# OECU_BASE5.net
KiCad netlist of a schematic drawn in Altium Designer
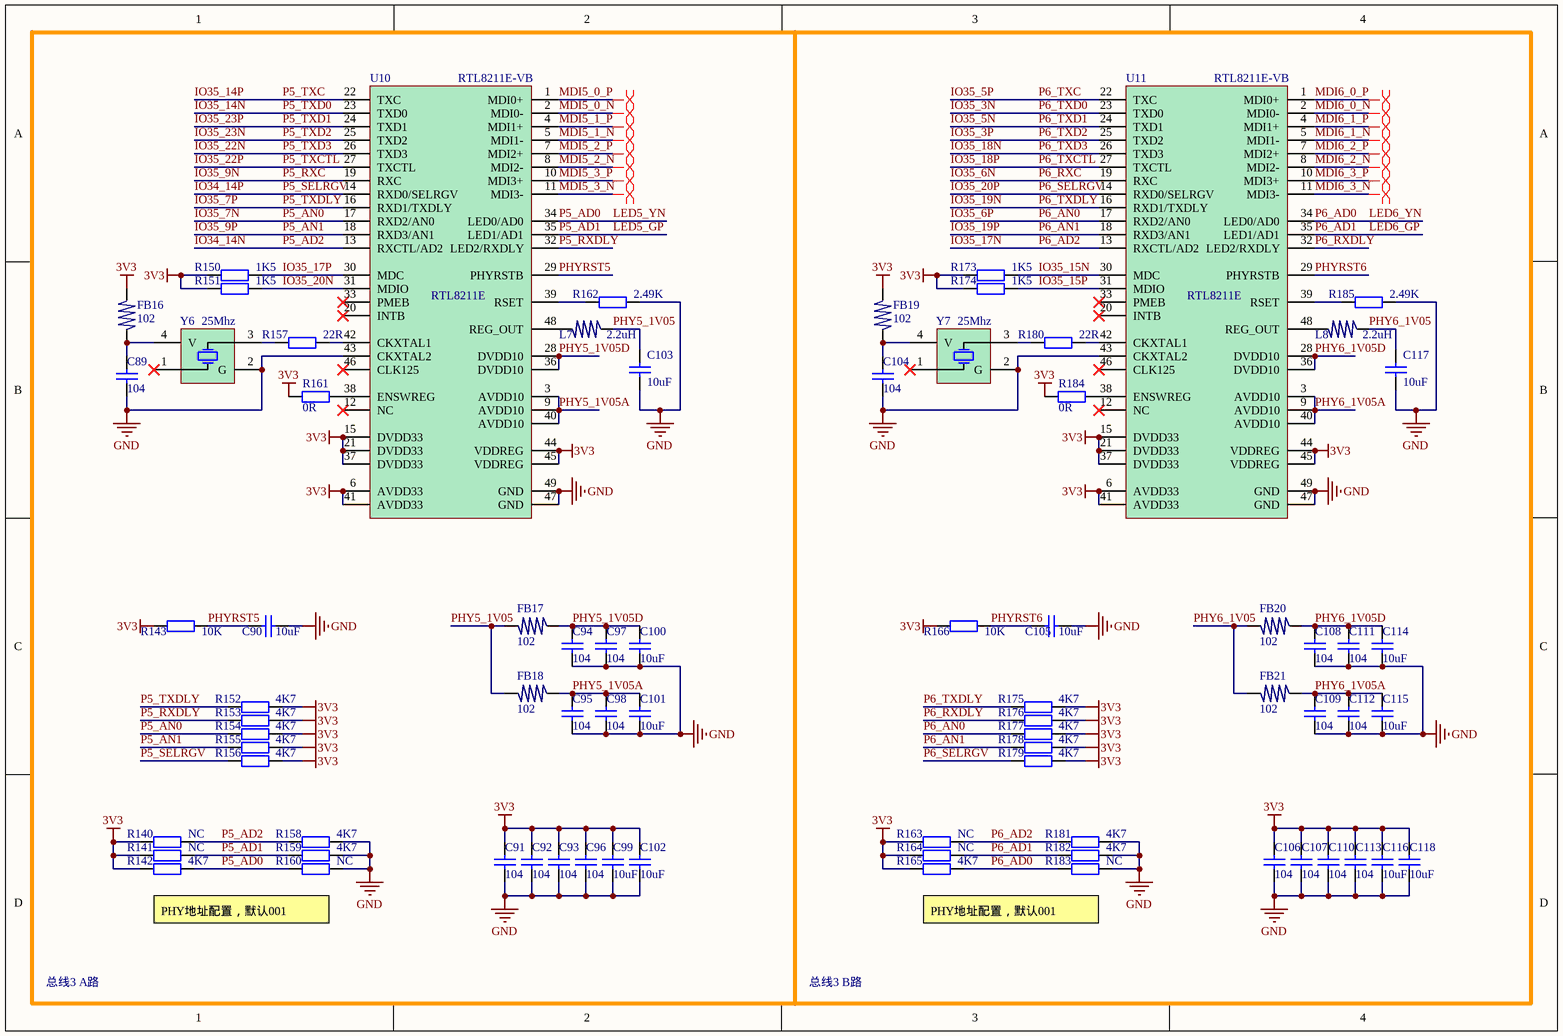
[diagram p0: OECU_BASE5.SchDoc]

(export (version "E")
  (design (tool "Eeschema 10.0.6"))
  (components
    (comp (ref "C89")
      (value "104")
      (footprint "0402")
      (description "贴片电容 0402")
      (libsource (lib "MT_Device") (part "CAP_0402"))
    )
    (comp (ref "C90")
      (value "10uF")
      (footprint "0402")
      (description "贴片电容 0402")
      (libsource (lib "MT_Device") (part "CAP_0402"))
    )
    (comp (ref "C91")
      (value "104")
      (footprint "0402")
      (description "贴片电容 0402")
      (libsource (lib "MT_Device") (part "CAP_0402"))
    )
    (comp (ref "C92")
      (value "104")
      (footprint "0402")
      (description "贴片电容 0402")
      (libsource (lib "MT_Device") (part "CAP_0402"))
    )
    (comp (ref "C93")
      (value "104")
      (footprint "0402")
      (description "贴片电容 0402")
      (libsource (lib "MT_Device") (part "CAP_0402"))
    )
    (comp (ref "C94")
      (value "104")
      (footprint "0402")
      (description "贴片电容 0402")
      (libsource (lib "MT_Device") (part "CAP_0402"))
    )
    (comp (ref "C95")
      (value "104")
      (footprint "0402")
      (description "贴片电容 0402")
      (libsource (lib "MT_Device") (part "CAP_0402"))
    )
    (comp (ref "C96")
      (value "104")
      (footprint "0402")
      (description "贴片电容 0402")
      (libsource (lib "MT_Device") (part "CAP_0402"))
    )
    (comp (ref "C97")
      (value "104")
      (footprint "0402")
      (description "贴片电容 0402")
      (libsource (lib "MT_Device") (part "CAP_0402"))
    )
    (comp (ref "C98")
      (value "104")
      (footprint "0402")
      (description "贴片电容 0402")
      (libsource (lib "MT_Device") (part "CAP_0402"))
    )
    (comp (ref "C99")
      (value "10uF")
      (footprint "0402")
      (description "贴片电容 0402")
      (libsource (lib "MT_Device") (part "CAP_0402"))
    )
    (comp (ref "C100")
      (value "10uF")
      (footprint "0402")
      (description "贴片电容 0402")
      (libsource (lib "MT_Device") (part "CAP_0402"))
    )
    (comp (ref "C101")
      (value "10uF")
      (footprint "0402")
      (description "贴片电容 0402")
      (libsource (lib "MT_Device") (part "CAP_0402"))
    )
    (comp (ref "C102")
      (value "10uF")
      (footprint "0402")
      (description "贴片电容 0402")
      (libsource (lib "MT_Device") (part "CAP_0402"))
    )
    (comp (ref "C103")
      (value "10uF")
      (footprint "0402")
      (description "贴片电容 0402")
      (libsource (lib "MT_Device") (part "CAP_0402"))
    )
    (comp (ref "C104")
      (value "104")
      (footprint "0402")
      (description "贴片电容 0402")
      (libsource (lib "MT_Device") (part "CAP_0402"))
    )
    (comp (ref "C105")
      (value "10uF")
      (footprint "0402")
      (description "贴片电容 0402")
      (libsource (lib "MT_Device") (part "CAP_0402"))
    )
    (comp (ref "C106")
      (value "104")
      (footprint "0402")
      (description "贴片电容 0402")
      (libsource (lib "MT_Device") (part "CAP_0402"))
    )
    (comp (ref "C107")
      (value "104")
      (footprint "0402")
      (description "贴片电容 0402")
      (libsource (lib "MT_Device") (part "CAP_0402"))
    )
    (comp (ref "C108")
      (value "104")
      (footprint "0402")
      (description "贴片电容 0402")
      (libsource (lib "MT_Device") (part "CAP_0402"))
    )
    (comp (ref "C109")
      (value "104")
      (footprint "0402")
      (description "贴片电容 0402")
      (libsource (lib "MT_Device") (part "CAP_0402"))
    )
    (comp (ref "C110")
      (value "104")
      (footprint "0402")
      (description "贴片电容 0402")
      (libsource (lib "MT_Device") (part "CAP_0402"))
    )
    (comp (ref "C111")
      (value "104")
      (footprint "0402")
      (description "贴片电容 0402")
      (libsource (lib "MT_Device") (part "CAP_0402"))
    )
    (comp (ref "C112")
      (value "104")
      (footprint "0402")
      (description "贴片电容 0402")
      (libsource (lib "MT_Device") (part "CAP_0402"))
    )
    (comp (ref "C113")
      (value "104")
      (footprint "0402")
      (description "贴片电容 0402")
      (libsource (lib "MT_Device") (part "CAP_0402"))
    )
    (comp (ref "C114")
      (value "10uF")
      (footprint "0402")
      (description "贴片电容 0402")
      (libsource (lib "MT_Device") (part "CAP_0402"))
    )
    (comp (ref "C115")
      (value "10uF")
      (footprint "0402")
      (description "贴片电容 0402")
      (libsource (lib "MT_Device") (part "CAP_0402"))
    )
    (comp (ref "C116")
      (value "10uF")
      (footprint "0402")
      (description "贴片电容 0402")
      (libsource (lib "MT_Device") (part "CAP_0402"))
    )
    (comp (ref "C117")
      (value "10uF")
      (footprint "0402")
      (description "贴片电容 0402")
      (libsource (lib "MT_Device") (part "CAP_0402"))
    )
    (comp (ref "C118")
      (value "10uF")
      (footprint "0402")
      (description "贴片电容 0402")
      (libsource (lib "MT_Device") (part "CAP_0402"))
    )
    (comp (ref "FB16")
      (value "102")
      (footprint "0402")
      (description "磁珠 0402")
      (libsource (lib "MT_Device") (part "FB_0402"))
    )
    (comp (ref "FB17")
      (value "102")
      (footprint "0603")
      (description "磁珠 0603")
      (libsource (lib "MT_Device") (part "FB_0603"))
    )
    (comp (ref "FB18")
      (value "102")
      (footprint "0603")
      (description "磁珠 0603")
      (libsource (lib "MT_Device") (part "FB_0603"))
    )
    (comp (ref "FB19")
      (value "102")
      (footprint "0402")
      (description "磁珠 0402")
      (libsource (lib "MT_Device") (part "FB_0402"))
    )
    (comp (ref "FB20")
      (value "102")
      (footprint "0603")
      (description "磁珠 0603")
      (libsource (lib "MT_Device") (part "FB_0603"))
    )
    (comp (ref "FB21")
      (value "102")
      (footprint "0603")
      (description "磁珠 0603")
      (libsource (lib "MT_Device") (part "FB_0603"))
    )
    (comp (ref "L7")
      (value "2.2uH")
      (footprint "0805")
      (description "电感 0805")
      (libsource (lib "MT_Device") (part "L_0805"))
    )
    (comp (ref "L8")
      (value "2.2uH")
      (footprint "0805")
      (description "电感 0805")
      (libsource (lib "MT_Device") (part "L_0805"))
    )
    (comp (ref "R140")
      (value "NC")
      (footprint "R_0402")
      (description "电阻 0402")
      (libsource (lib "MT_Device") (part "RES_0402"))
    )
    (comp (ref "R141")
      (value "NC")
      (footprint "R_0402")
      (description "电阻 0402")
      (libsource (lib "MT_Device") (part "RES_0402"))
    )
    (comp (ref "R142")
      (value "4K7")
      (footprint "R_0402")
      (description "电阻 0402")
      (libsource (lib "MT_Device") (part "RES_0402"))
    )
    (comp (ref "R143")
      (value "10K")
      (footprint "R_0402")
      (description "电阻 0402")
      (libsource (lib "MT_Device") (part "RES_0402"))
    )
    (comp (ref "R150")
      (value "1K5")
      (footprint "R_0402")
      (description "电阻 0402")
      (libsource (lib "") (part "RES_0402_1"))
    )
    (comp (ref "R151")
      (value "1K5")
      (footprint "R_0402")
      (description "电阻 0402")
      (libsource (lib "") (part "RES_0402_1"))
    )
    (comp (ref "R152")
      (value "4K7")
      (footprint "R_0402")
      (description "电阻 0402")
      (libsource (lib "MT_Device") (part "RES_0402"))
    )
    (comp (ref "R153")
      (value "4K7")
      (footprint "R_0402")
      (description "电阻 0402")
      (libsource (lib "MT_Device") (part "RES_0402"))
    )
    (comp (ref "R154")
      (value "4K7")
      (footprint "R_0402")
      (description "电阻 0402")
      (libsource (lib "MT_Device") (part "RES_0402"))
    )
    (comp (ref "R155")
      (value "4K7")
      (footprint "R_0402")
      (description "电阻 0402")
      (libsource (lib "MT_Device") (part "RES_0402"))
    )
    (comp (ref "R156")
      (value "4K7")
      (footprint "R_0402")
      (description "电阻 0402")
      (libsource (lib "MT_Device") (part "RES_0402"))
    )
    (comp (ref "R157")
      (value "22R")
      (footprint "R_0402")
      (description "电阻 0402")
      (libsource (lib "") (part "RES_0402_1"))
    )
    (comp (ref "R158")
      (value "4K7")
      (footprint "R_0402")
      (description "电阻 0402")
      (libsource (lib "MT_Device") (part "RES_0402"))
    )
    (comp (ref "R159")
      (value "4K7")
      (footprint "R_0402")
      (description "电阻 0402")
      (libsource (lib "MT_Device") (part "RES_0402"))
    )
    (comp (ref "R160")
      (value "NC")
      (footprint "R_0402")
      (description "电阻 0402")
      (libsource (lib "MT_Device") (part "RES_0402"))
    )
    (comp (ref "R161")
      (value "0R")
      (footprint "R_0402")
      (description "电阻 0402")
      (libsource (lib "") (part "RES_0402_1"))
    )
    (comp (ref "R162")
      (value "2.49K")
      (footprint "R_0402")
      (description "电阻 0402")
      (libsource (lib "MT_Device") (part "RES_0402"))
    )
    (comp (ref "R163")
      (value "NC")
      (footprint "R_0402")
      (description "电阻 0402")
      (libsource (lib "MT_Device") (part "RES_0402"))
    )
    (comp (ref "R164")
      (value "NC")
      (footprint "R_0402")
      (description "电阻 0402")
      (libsource (lib "MT_Device") (part "RES_0402"))
    )
    (comp (ref "R165")
      (value "4K7")
      (footprint "R_0402")
      (description "电阻 0402")
      (libsource (lib "MT_Device") (part "RES_0402"))
    )
    (comp (ref "R166")
      (value "10K")
      (footprint "R_0402")
      (description "电阻 0402")
      (libsource (lib "MT_Device") (part "RES_0402"))
    )
    (comp (ref "R173")
      (value "1K5")
      (footprint "R_0402")
      (description "电阻 0402")
      (libsource (lib "") (part "RES_0402_1"))
    )
    (comp (ref "R174")
      (value "1K5")
      (footprint "R_0402")
      (description "电阻 0402")
      (libsource (lib "") (part "RES_0402_1"))
    )
    (comp (ref "R175")
      (value "4K7")
      (footprint "R_0402")
      (description "电阻 0402")
      (libsource (lib "MT_Device") (part "RES_0402"))
    )
    (comp (ref "R176")
      (value "4K7")
      (footprint "R_0402")
      (description "电阻 0402")
      (libsource (lib "MT_Device") (part "RES_0402"))
    )
    (comp (ref "R177")
      (value "4K7")
      (footprint "R_0402")
      (description "电阻 0402")
      (libsource (lib "MT_Device") (part "RES_0402"))
    )
    (comp (ref "R178")
      (value "4K7")
      (footprint "R_0402")
      (description "电阻 0402")
      (libsource (lib "MT_Device") (part "RES_0402"))
    )
    (comp (ref "R179")
      (value "4K7")
      (footprint "R_0402")
      (description "电阻 0402")
      (libsource (lib "MT_Device") (part "RES_0402"))
    )
    (comp (ref "R180")
      (value "22R")
      (footprint "R_0402")
      (description "电阻 0402")
      (libsource (lib "") (part "RES_0402_1"))
    )
    (comp (ref "R181")
      (value "4K7")
      (footprint "R_0402")
      (description "电阻 0402")
      (libsource (lib "MT_Device") (part "RES_0402"))
    )
    (comp (ref "R182")
      (value "4K7")
      (footprint "R_0402")
      (description "电阻 0402")
      (libsource (lib "MT_Device") (part "RES_0402"))
    )
    (comp (ref "R183")
      (value "NC")
      (footprint "R_0402")
      (description "电阻 0402")
      (libsource (lib "MT_Device") (part "RES_0402"))
    )
    (comp (ref "R184")
      (value "0R")
      (footprint "R_0402")
      (description "电阻 0402")
      (libsource (lib "") (part "RES_0402_1"))
    )
    (comp (ref "R185")
      (value "2.49K")
      (footprint "R_0402")
      (description "电阻 0402")
      (libsource (lib "MT_Device") (part "RES_0402"))
    )
    (comp (ref "U10")
      (value "RTL8211E-VB")
      (footprint "QFN48")
      (description "QFN48")
      (libsource (lib "MT_Chip") (part "RTL8211E"))
    )
    (comp (ref "U11")
      (value "RTL8211E-VB")
      (footprint "QFN48")
      (description "QFN48")
      (libsource (lib "MT_Chip") (part "RTL8211E"))
    )
    (comp (ref "Y6") (value "25Mhz") (footprint "XTAL_3225") (libsource (lib "MT_Device") (part "XTAL_3225")))
    (comp (ref "Y7") (value "25Mhz") (footprint "XTAL_3225") (libsource (lib "MT_Device") (part "XTAL_3225")))
  )
  (nets
    (net (code "1") (name "/IO34_14N") (class "Default")
      (node (ref "R140") (pin "2") (pinfunction "2_2") (pintype "passive"))
      (node (ref "R158") (pin "1") (pinfunction "1_1") (pintype "passive"))
      (node (ref "U10") (pin "13") (pinfunction "RXCTL/AD2_13") (pintype "passive"))
    )
    (net (code "2") (name "/IO34_14P") (class "Default")
      (node (ref "R156") (pin "1") (pinfunction "1_1") (pintype "passive"))
      (node (ref "U10") (pin "14") (pinfunction "RXD0/SELRGV_14") (pintype "passive"))
    )
    (net (code "3") (name "/IO35_3N") (class "Default")
      (node (ref "U11") (pin "23") (pinfunction "TXD0_23") (pintype "passive"))
    )
    (net (code "4") (name "/IO35_3P") (class "Default")
      (node (ref "U11") (pin "25") (pinfunction "TXD2_25") (pintype "passive"))
    )
    (net (code "5") (name "/IO35_5N") (class "Default")
      (node (ref "U11") (pin "24") (pinfunction "TXD1_24") (pintype "passive"))
    )
    (net (code "6") (name "/IO35_5P") (class "Default")
      (node (ref "U11") (pin "22") (pinfunction "TXC_22") (pintype "passive"))
    )
    (net (code "7") (name "/IO35_6N") (class "Default")
      (node (ref "U11") (pin "19") (pinfunction "RXC_19") (pintype "passive"))
    )
    (net (code "8") (name "/IO35_6P") (class "Default")
      (node (ref "R177") (pin "1") (pinfunction "1_1") (pintype "passive"))
      (node (ref "U11") (pin "17") (pinfunction "RXD2/AN0_17") (pintype "passive"))
    )
    (net (code "9") (name "/IO35_7N") (class "Default")
      (node (ref "R154") (pin "1") (pinfunction "1_1") (pintype "passive"))
      (node (ref "U10") (pin "17") (pinfunction "RXD2/AN0_17") (pintype "passive"))
    )
    (net (code "10") (name "/IO35_7P") (class "Default")
      (node (ref "R152") (pin "1") (pinfunction "1_1") (pintype "passive"))
      (node (ref "U10") (pin "16") (pinfunction "RXD1/TXDLY_16") (pintype "passive"))
    )
    (net (code "11") (name "/IO35_9N") (class "Default")
      (node (ref "U10") (pin "19") (pinfunction "RXC_19") (pintype "passive"))
    )
    (net (code "12") (name "/IO35_9P") (class "Default")
      (node (ref "R155") (pin "1") (pinfunction "1_1") (pintype "passive"))
      (node (ref "U10") (pin "18") (pinfunction "RXD3/AN1_18") (pintype "passive"))
    )
    (net (code "13") (name "/IO35_14N") (class "Default")
      (node (ref "U10") (pin "23") (pinfunction "TXD0_23") (pintype "passive"))
    )
    (net (code "14") (name "/IO35_14P") (class "Default")
      (node (ref "U10") (pin "22") (pinfunction "TXC_22") (pintype "passive"))
    )
    (net (code "15") (name "/IO35_15N") (class "Default")
      (node (ref "R173") (pin "1") (pinfunction "1_1") (pintype "passive"))
      (node (ref "U11") (pin "30") (pinfunction "MDC_30") (pintype "passive"))
    )
    (net (code "16") (name "/IO35_15P") (class "Default")
      (node (ref "R174") (pin "1") (pinfunction "1_1") (pintype "passive"))
      (node (ref "U11") (pin "31") (pinfunction "MDIO_31") (pintype "passive"))
    )
    (net (code "17") (name "/IO35_17N") (class "Default")
      (node (ref "R163") (pin "2") (pinfunction "2_2") (pintype "passive"))
      (node (ref "R181") (pin "1") (pinfunction "1_1") (pintype "passive"))
      (node (ref "U11") (pin "13") (pinfunction "RXCTL/AD2_13") (pintype "passive"))
    )
    (net (code "18") (name "/IO35_17P") (class "Default")
      (node (ref "R150") (pin "1") (pinfunction "1_1") (pintype "passive"))
      (node (ref "U10") (pin "30") (pinfunction "MDC_30") (pintype "passive"))
    )
    (net (code "19") (name "/IO35_18N") (class "Default")
      (node (ref "U11") (pin "26") (pinfunction "TXD3_26") (pintype "passive"))
    )
    (net (code "20") (name "/IO35_18P") (class "Default")
      (node (ref "U11") (pin "27") (pinfunction "TXCTL_27") (pintype "passive"))
    )
    (net (code "21") (name "/IO35_19N") (class "Default")
      (node (ref "R175") (pin "1") (pinfunction "1_1") (pintype "passive"))
      (node (ref "U11") (pin "16") (pinfunction "RXD1/TXDLY_16") (pintype "passive"))
    )
    (net (code "22") (name "/IO35_19P") (class "Default")
      (node (ref "R178") (pin "1") (pinfunction "1_1") (pintype "passive"))
      (node (ref "U11") (pin "18") (pinfunction "RXD3/AN1_18") (pintype "passive"))
    )
    (net (code "23") (name "/IO35_20N") (class "Default")
      (node (ref "R151") (pin "1") (pinfunction "1_1") (pintype "passive"))
      (node (ref "U10") (pin "31") (pinfunction "MDIO_31") (pintype "passive"))
    )
    (net (code "24") (name "/IO35_20P") (class "Default")
      (node (ref "R179") (pin "1") (pinfunction "1_1") (pintype "passive"))
      (node (ref "U11") (pin "14") (pinfunction "RXD0/SELRGV_14") (pintype "passive"))
    )
    (net (code "25") (name "/IO35_22N") (class "Default")
      (node (ref "U10") (pin "26") (pinfunction "TXD3_26") (pintype "passive"))
    )
    (net (code "26") (name "/IO35_22P") (class "Default")
      (node (ref "U10") (pin "27") (pinfunction "TXCTL_27") (pintype "passive"))
    )
    (net (code "27") (name "/IO35_23N") (class "Default")
      (node (ref "U10") (pin "25") (pinfunction "TXD2_25") (pintype "passive"))
    )
    (net (code "28") (name "/IO35_23P") (class "Default")
      (node (ref "U10") (pin "24") (pinfunction "TXD1_24") (pintype "passive"))
    )
    (net (code "29") (name "/LED5_GP") (class "Default")
      (node (ref "R141") (pin "2") (pinfunction "2_2") (pintype "passive"))
      (node (ref "R159") (pin "1") (pinfunction "1_1") (pintype "passive"))
      (node (ref "U10") (pin "35") (pinfunction "LED1/AD1_35") (pintype "passive"))
    )
    (net (code "30") (name "/LED5_YN") (class "Default")
      (node (ref "R142") (pin "2") (pinfunction "2_2") (pintype "passive"))
      (node (ref "R160") (pin "1") (pinfunction "1_1") (pintype "passive"))
      (node (ref "U10") (pin "34") (pinfunction "LED0/AD0_34") (pintype "passive"))
    )
    (net (code "31") (name "/LED6_GP") (class "Default")
      (node (ref "R164") (pin "2") (pinfunction "2_2") (pintype "passive"))
      (node (ref "R182") (pin "1") (pinfunction "1_1") (pintype "passive"))
      (node (ref "U11") (pin "35") (pinfunction "LED1/AD1_35") (pintype "passive"))
    )
    (net (code "32") (name "/LED6_YN") (class "Default")
      (node (ref "R165") (pin "2") (pinfunction "2_2") (pintype "passive"))
      (node (ref "R183") (pin "1") (pinfunction "1_1") (pintype "passive"))
      (node (ref "U11") (pin "34") (pinfunction "LED0/AD0_34") (pintype "passive"))
    )
    (net (code "33") (name "/MDI5_0_N") (class "Default")
      (node (ref "U10") (pin "2") (pinfunction "MDI0-_2") (pintype "passive"))
    )
    (net (code "34") (name "/MDI5_0_P") (class "Default")
      (node (ref "U10") (pin "1") (pinfunction "MDI0+_1") (pintype "passive"))
    )
    (net (code "35") (name "/MDI5_1_N") (class "Default")
      (node (ref "U10") (pin "5") (pinfunction "MDI1-_5") (pintype "passive"))
    )
    (net (code "36") (name "/MDI5_1_P") (class "Default")
      (node (ref "U10") (pin "4") (pinfunction "MDI1+_4") (pintype "passive"))
    )
    (net (code "37") (name "/MDI5_2_N") (class "Default")
      (node (ref "U10") (pin "8") (pinfunction "MDI2-_8") (pintype "passive"))
    )
    (net (code "38") (name "/MDI5_2_P") (class "Default")
      (node (ref "U10") (pin "7") (pinfunction "MDI2+_7") (pintype "passive"))
    )
    (net (code "39") (name "/MDI5_3_N") (class "Default")
      (node (ref "U10") (pin "11") (pinfunction "MDI3-_11") (pintype "passive"))
    )
    (net (code "40") (name "/MDI5_3_P") (class "Default")
      (node (ref "U10") (pin "10") (pinfunction "MDI3+_10") (pintype "passive"))
    )
    (net (code "41") (name "/MDI6_0_N") (class "Default")
      (node (ref "U11") (pin "2") (pinfunction "MDI0-_2") (pintype "passive"))
    )
    (net (code "42") (name "/MDI6_0_P") (class "Default")
      (node (ref "U11") (pin "1") (pinfunction "MDI0+_1") (pintype "passive"))
    )
    (net (code "43") (name "/MDI6_1_N") (class "Default")
      (node (ref "U11") (pin "5") (pinfunction "MDI1-_5") (pintype "passive"))
    )
    (net (code "44") (name "/MDI6_1_P") (class "Default")
      (node (ref "U11") (pin "4") (pinfunction "MDI1+_4") (pintype "passive"))
    )
    (net (code "45") (name "/MDI6_2_N") (class "Default")
      (node (ref "U11") (pin "8") (pinfunction "MDI2-_8") (pintype "passive"))
    )
    (net (code "46") (name "/MDI6_2_P") (class "Default")
      (node (ref "U11") (pin "7") (pinfunction "MDI2+_7") (pintype "passive"))
    )
    (net (code "47") (name "/MDI6_3_N") (class "Default")
      (node (ref "U11") (pin "11") (pinfunction "MDI3-_11") (pintype "passive"))
    )
    (net (code "48") (name "/MDI6_3_P") (class "Default")
      (node (ref "U11") (pin "10") (pinfunction "MDI3+_10") (pintype "passive"))
    )
    (net (code "49") (name "/P5_RXDLY") (class "Default")
      (node (ref "R153") (pin "1") (pinfunction "1_1") (pintype "passive"))
      (node (ref "U10") (pin "32") (pinfunction "LED2/RXDLY_32") (pintype "passive"))
    )
    (net (code "50") (name "/P6_RXDLY") (class "Default")
      (node (ref "R176") (pin "1") (pinfunction "1_1") (pintype "passive"))
      (node (ref "U11") (pin "32") (pinfunction "LED2/RXDLY_32") (pintype "passive"))
    )
    (net (code "51") (name "/PHY5_1V05") (class "Default")
      (node (ref "C103") (pin "2") (pinfunction "2_2") (pintype "passive"))
      (node (ref "FB17") (pin "1") (pintype "passive"))
      (node (ref "FB18") (pin "1") (pintype "passive"))
      (node (ref "L7") (pin "1") (pintype "passive"))
    )
    (net (code "52") (name "/PHY5_1V05A") (class "Default")
      (node (ref "C101") (pin "2") (pinfunction "2_2") (pintype "passive"))
      (node (ref "C95") (pin "2") (pinfunction "2_2") (pintype "passive"))
      (node (ref "C98") (pin "2") (pinfunction "2_2") (pintype "passive"))
      (node (ref "FB18") (pin "2") (pintype "passive"))
      (node (ref "U10") (pin "3") (pinfunction "AVDD10_3") (pintype "passive"))
      (node (ref "U10") (pin "40") (pinfunction "AVDD10_40") (pintype "passive"))
      (node (ref "U10") (pin "9") (pinfunction "AVDD10_9") (pintype "passive"))
    )
    (net (code "53") (name "/PHY5_1V05D") (class "Default")
      (node (ref "C100") (pin "2") (pinfunction "2_2") (pintype "passive"))
      (node (ref "C94") (pin "2") (pinfunction "2_2") (pintype "passive"))
      (node (ref "C97") (pin "2") (pinfunction "2_2") (pintype "passive"))
      (node (ref "FB17") (pin "2") (pintype "passive"))
      (node (ref "U10") (pin "28") (pinfunction "DVDD10_28") (pintype "passive"))
      (node (ref "U10") (pin "36") (pinfunction "DVDD10_36") (pintype "passive"))
    )
    (net (code "54") (name "/PHY6_1V05") (class "Default")
      (node (ref "C117") (pin "2") (pinfunction "2_2") (pintype "passive"))
      (node (ref "FB20") (pin "1") (pintype "passive"))
      (node (ref "FB21") (pin "1") (pintype "passive"))
      (node (ref "L8") (pin "1") (pintype "passive"))
    )
    (net (code "55") (name "/PHY6_1V05A") (class "Default")
      (node (ref "C109") (pin "2") (pinfunction "2_2") (pintype "passive"))
      (node (ref "C112") (pin "2") (pinfunction "2_2") (pintype "passive"))
      (node (ref "C115") (pin "2") (pinfunction "2_2") (pintype "passive"))
      (node (ref "FB21") (pin "2") (pintype "passive"))
      (node (ref "U11") (pin "3") (pinfunction "AVDD10_3") (pintype "passive"))
      (node (ref "U11") (pin "40") (pinfunction "AVDD10_40") (pintype "passive"))
      (node (ref "U11") (pin "9") (pinfunction "AVDD10_9") (pintype "passive"))
    )
    (net (code "56") (name "/PHY6_1V05D") (class "Default")
      (node (ref "C108") (pin "2") (pinfunction "2_2") (pintype "passive"))
      (node (ref "C111") (pin "2") (pinfunction "2_2") (pintype "passive"))
      (node (ref "C114") (pin "2") (pinfunction "2_2") (pintype "passive"))
      (node (ref "FB20") (pin "2") (pintype "passive"))
      (node (ref "U11") (pin "28") (pinfunction "DVDD10_28") (pintype "passive"))
      (node (ref "U11") (pin "36") (pinfunction "DVDD10_36") (pintype "passive"))
    )
    (net (code "57") (name "/PHYRST5") (class "Default")
      (node (ref "C90") (pin "1") (pinfunction "1_1") (pintype "passive"))
      (node (ref "R143") (pin "2") (pinfunction "2_2") (pintype "passive"))
      (node (ref "U10") (pin "29") (pinfunction "PHYRSTB_29") (pintype "passive"))
    )
    (net (code "58") (name "/PHYRST6") (class "Default")
      (node (ref "C105") (pin "1") (pinfunction "1_1") (pintype "passive"))
      (node (ref "R166") (pin "2") (pinfunction "2_2") (pintype "passive"))
      (node (ref "U11") (pin "29") (pinfunction "PHYRSTB_29") (pintype "passive"))
    )
    (net (code "59") (name "3V3") (class "Default")
      (node (ref "C102") (pin "1") (pinfunction "1_1") (pintype "passive"))
      (node (ref "C106") (pin "1") (pinfunction "1_1") (pintype "passive"))
      (node (ref "C107") (pin "1") (pinfunction "1_1") (pintype "passive"))
      (node (ref "C110") (pin "1") (pinfunction "1_1") (pintype "passive"))
      (node (ref "C113") (pin "1") (pinfunction "1_1") (pintype "passive"))
      (node (ref "C116") (pin "1") (pinfunction "1_1") (pintype "passive"))
      (node (ref "C118") (pin "1") (pinfunction "1_1") (pintype "passive"))
      (node (ref "C91") (pin "1") (pinfunction "1_1") (pintype "passive"))
      (node (ref "C92") (pin "1") (pinfunction "1_1") (pintype "passive"))
      (node (ref "C93") (pin "1") (pinfunction "1_1") (pintype "passive"))
      (node (ref "C96") (pin "1") (pinfunction "1_1") (pintype "passive"))
      (node (ref "C99") (pin "1") (pinfunction "1_1") (pintype "passive"))
      (node (ref "FB16") (pin "2") (pintype "passive"))
      (node (ref "FB19") (pin "2") (pintype "passive"))
      (node (ref "R140") (pin "1") (pinfunction "1_1") (pintype "passive"))
      (node (ref "R141") (pin "1") (pinfunction "1_1") (pintype "passive"))
      (node (ref "R142") (pin "1") (pinfunction "1_1") (pintype "passive"))
      (node (ref "R143") (pin "1") (pinfunction "1_1") (pintype "passive"))
      (node (ref "R150") (pin "2") (pinfunction "2_2") (pintype "passive"))
      (node (ref "R151") (pin "2") (pinfunction "2_2") (pintype "passive"))
      (node (ref "R152") (pin "2") (pinfunction "2_2") (pintype "passive"))
      (node (ref "R153") (pin "2") (pinfunction "2_2") (pintype "passive"))
      (node (ref "R154") (pin "2") (pinfunction "2_2") (pintype "passive"))
      (node (ref "R155") (pin "2") (pinfunction "2_2") (pintype "passive"))
      (node (ref "R156") (pin "2") (pinfunction "2_2") (pintype "passive"))
      (node (ref "R161") (pin "2") (pinfunction "2_2") (pintype "passive"))
      (node (ref "R163") (pin "1") (pinfunction "1_1") (pintype "passive"))
      (node (ref "R164") (pin "1") (pinfunction "1_1") (pintype "passive"))
      (node (ref "R165") (pin "1") (pinfunction "1_1") (pintype "passive"))
      (node (ref "R166") (pin "1") (pinfunction "1_1") (pintype "passive"))
      (node (ref "R173") (pin "2") (pinfunction "2_2") (pintype "passive"))
      (node (ref "R174") (pin "2") (pinfunction "2_2") (pintype "passive"))
      (node (ref "R175") (pin "2") (pinfunction "2_2") (pintype "passive"))
      (node (ref "R176") (pin "2") (pinfunction "2_2") (pintype "passive"))
      (node (ref "R177") (pin "2") (pinfunction "2_2") (pintype "passive"))
      (node (ref "R178") (pin "2") (pinfunction "2_2") (pintype "passive"))
      (node (ref "R179") (pin "2") (pinfunction "2_2") (pintype "passive"))
      (node (ref "R184") (pin "2") (pinfunction "2_2") (pintype "passive"))
      (node (ref "U10") (pin "15") (pinfunction "DVDD33_15") (pintype "passive"))
      (node (ref "U10") (pin "21") (pinfunction "DVDD33_21") (pintype "passive"))
      (node (ref "U10") (pin "37") (pinfunction "DVDD33_37") (pintype "passive"))
      (node (ref "U10") (pin "41") (pinfunction "AVDD33_41") (pintype "passive"))
      (node (ref "U10") (pin "44") (pinfunction "VDDREG_44") (pintype "passive"))
      (node (ref "U10") (pin "45") (pinfunction "VDDREG_45") (pintype "passive"))
      (node (ref "U10") (pin "6") (pinfunction "AVDD33_6") (pintype "passive"))
      (node (ref "U11") (pin "15") (pinfunction "DVDD33_15") (pintype "passive"))
      (node (ref "U11") (pin "21") (pinfunction "DVDD33_21") (pintype "passive"))
      (node (ref "U11") (pin "37") (pinfunction "DVDD33_37") (pintype "passive"))
      (node (ref "U11") (pin "41") (pinfunction "AVDD33_41") (pintype "passive"))
      (node (ref "U11") (pin "44") (pinfunction "VDDREG_44") (pintype "passive"))
      (node (ref "U11") (pin "45") (pinfunction "VDDREG_45") (pintype "passive"))
      (node (ref "U11") (pin "6") (pinfunction "AVDD33_6") (pintype "passive"))
    )
    (net (code "60") (name "GND") (class "Default")
      (node (ref "C100") (pin "1") (pinfunction "1_1") (pintype "passive"))
      (node (ref "C101") (pin "1") (pinfunction "1_1") (pintype "passive"))
      (node (ref "C102") (pin "2") (pinfunction "2_2") (pintype "passive"))
      (node (ref "C103") (pin "1") (pinfunction "1_1") (pintype "passive"))
      (node (ref "C104") (pin "1") (pinfunction "1_1") (pintype "passive"))
      (node (ref "C105") (pin "2") (pinfunction "2_2") (pintype "passive"))
      (node (ref "C106") (pin "2") (pinfunction "2_2") (pintype "passive"))
      (node (ref "C107") (pin "2") (pinfunction "2_2") (pintype "passive"))
      (node (ref "C108") (pin "1") (pinfunction "1_1") (pintype "passive"))
      (node (ref "C109") (pin "1") (pinfunction "1_1") (pintype "passive"))
      (node (ref "C110") (pin "2") (pinfunction "2_2") (pintype "passive"))
      (node (ref "C111") (pin "1") (pinfunction "1_1") (pintype "passive"))
      (node (ref "C112") (pin "1") (pinfunction "1_1") (pintype "passive"))
      (node (ref "C113") (pin "2") (pinfunction "2_2") (pintype "passive"))
      (node (ref "C114") (pin "1") (pinfunction "1_1") (pintype "passive"))
      (node (ref "C115") (pin "1") (pinfunction "1_1") (pintype "passive"))
      (node (ref "C116") (pin "2") (pinfunction "2_2") (pintype "passive"))
      (node (ref "C117") (pin "1") (pinfunction "1_1") (pintype "passive"))
      (node (ref "C118") (pin "2") (pinfunction "2_2") (pintype "passive"))
      (node (ref "C89") (pin "1") (pinfunction "1_1") (pintype "passive"))
      (node (ref "C90") (pin "2") (pinfunction "2_2") (pintype "passive"))
      (node (ref "C91") (pin "2") (pinfunction "2_2") (pintype "passive"))
      (node (ref "C92") (pin "2") (pinfunction "2_2") (pintype "passive"))
      (node (ref "C93") (pin "2") (pinfunction "2_2") (pintype "passive"))
      (node (ref "C94") (pin "1") (pinfunction "1_1") (pintype "passive"))
      (node (ref "C95") (pin "1") (pinfunction "1_1") (pintype "passive"))
      (node (ref "C96") (pin "2") (pinfunction "2_2") (pintype "passive"))
      (node (ref "C97") (pin "1") (pinfunction "1_1") (pintype "passive"))
      (node (ref "C98") (pin "1") (pinfunction "1_1") (pintype "passive"))
      (node (ref "C99") (pin "2") (pinfunction "2_2") (pintype "passive"))
      (node (ref "R158") (pin "2") (pinfunction "2_2") (pintype "passive"))
      (node (ref "R159") (pin "2") (pinfunction "2_2") (pintype "passive"))
      (node (ref "R160") (pin "2") (pinfunction "2_2") (pintype "passive"))
      (node (ref "R162") (pin "2") (pinfunction "2_2") (pintype "passive"))
      (node (ref "R181") (pin "2") (pinfunction "2_2") (pintype "passive"))
      (node (ref "R182") (pin "2") (pinfunction "2_2") (pintype "passive"))
      (node (ref "R183") (pin "2") (pinfunction "2_2") (pintype "passive"))
      (node (ref "R185") (pin "2") (pinfunction "2_2") (pintype "passive"))
      (node (ref "U10") (pin "43") (pinfunction "CKXTAL2_43") (pintype "passive"))
      (node (ref "U10") (pin "47") (pinfunction "GND_47") (pintype "passive"))
      (node (ref "U10") (pin "49") (pinfunction "GND_49") (pintype "passive"))
      (node (ref "U11") (pin "43") (pinfunction "CKXTAL2_43") (pintype "passive"))
      (node (ref "U11") (pin "47") (pinfunction "GND_47") (pintype "passive"))
      (node (ref "U11") (pin "49") (pinfunction "GND_49") (pintype "passive"))
      (node (ref "Y6") (pin "2") (pinfunction "G_2") (pintype "passive"))
      (node (ref "Y7") (pin "2") (pinfunction "G_2") (pintype "passive"))
    )
    (net (code "61") (name "Net-(U10-CKXTAL1)") (class "Default")
      (node (ref "R157") (pin "1") (pinfunction "1_1") (pintype "passive"))
      (node (ref "U10") (pin "42") (pinfunction "CKXTAL1_42") (pintype "passive"))
    )
    (net (code "62") (name "Net-(U10-ENSWREG)") (class "Default")
      (node (ref "R161") (pin "1") (pinfunction "1_1") (pintype "passive"))
      (node (ref "U10") (pin "38") (pinfunction "ENSWREG_38") (pintype "passive"))
    )
    (net (code "63") (name "Net-(U10-REG_OUT)") (class "Default")
      (node (ref "L7") (pin "2") (pintype "passive"))
      (node (ref "U10") (pin "48") (pinfunction "REG_OUT_48") (pintype "passive"))
    )
    (net (code "64") (name "Net-(U10-RSET)") (class "Default")
      (node (ref "R162") (pin "1") (pinfunction "1_1") (pintype "passive"))
      (node (ref "U10") (pin "39") (pinfunction "RSET_39") (pintype "passive"))
    )
    (net (code "65") (name "Net-(U11-CKXTAL1)") (class "Default")
      (node (ref "R180") (pin "1") (pinfunction "1_1") (pintype "passive"))
      (node (ref "U11") (pin "42") (pinfunction "CKXTAL1_42") (pintype "passive"))
    )
    (net (code "66") (name "Net-(U11-ENSWREG)") (class "Default")
      (node (ref "R184") (pin "1") (pinfunction "1_1") (pintype "passive"))
      (node (ref "U11") (pin "38") (pinfunction "ENSWREG_38") (pintype "passive"))
    )
    (net (code "67") (name "Net-(U11-REG_OUT)") (class "Default")
      (node (ref "L8") (pin "2") (pintype "passive"))
      (node (ref "U11") (pin "48") (pinfunction "REG_OUT_48") (pintype "passive"))
    )
    (net (code "68") (name "Net-(U11-RSET)") (class "Default")
      (node (ref "R185") (pin "1") (pinfunction "1_1") (pintype "passive"))
      (node (ref "U11") (pin "39") (pinfunction "RSET_39") (pintype "passive"))
    )
    (net (code "69") (name "Net-(Y6-OP)") (class "Default")
      (node (ref "R157") (pin "2") (pinfunction "2_2") (pintype "passive"))
      (node (ref "Y6") (pin "3") (pinfunction "OP_3") (pintype "passive"))
    )
    (net (code "70") (name "Net-(Y6-V)") (class "Default")
      (node (ref "C89") (pin "2") (pinfunction "2_2") (pintype "passive"))
      (node (ref "FB16") (pin "1") (pintype "passive"))
      (node (ref "Y6") (pin "4") (pinfunction "V_4") (pintype "passive"))
    )
    (net (code "71") (name "Net-(Y7-OP)") (class "Default")
      (node (ref "R180") (pin "2") (pinfunction "2_2") (pintype "passive"))
      (node (ref "Y7") (pin "3") (pinfunction "OP_3") (pintype "passive"))
    )
    (net (code "72") (name "Net-(Y7-V)") (class "Default")
      (node (ref "C104") (pin "2") (pinfunction "2_2") (pintype "passive"))
      (node (ref "FB19") (pin "1") (pintype "passive"))
      (node (ref "Y7") (pin "4") (pinfunction "V_4") (pintype "passive"))
    )
    (net (code "73") (name "unconnected-(U10-CLK125-Pad46)") (class "Default")
      (node (ref "U10") (pin "46") (pinfunction "CLK125_46") (pintype "passive+no_connect"))
    )
    (net (code "74") (name "unconnected-(U10-INTB-Pad20)") (class "Default")
      (node (ref "U10") (pin "20") (pinfunction "INTB_20") (pintype "passive+no_connect"))
    )
    (net (code "75") (name "unconnected-(U10-NC-Pad12)") (class "Default")
      (node (ref "U10") (pin "12") (pinfunction "NC_12") (pintype "passive+no_connect"))
    )
    (net (code "76") (name "unconnected-(U10-PMEB-Pad33)") (class "Default")
      (node (ref "U10") (pin "33") (pinfunction "PMEB_33") (pintype "passive+no_connect"))
    )
    (net (code "77") (name "unconnected-(U11-CLK125-Pad46)") (class "Default")
      (node (ref "U11") (pin "46") (pinfunction "CLK125_46") (pintype "passive+no_connect"))
    )
    (net (code "78") (name "unconnected-(U11-INTB-Pad20)") (class "Default")
      (node (ref "U11") (pin "20") (pinfunction "INTB_20") (pintype "passive+no_connect"))
    )
    (net (code "79") (name "unconnected-(U11-NC-Pad12)") (class "Default")
      (node (ref "U11") (pin "12") (pinfunction "NC_12") (pintype "passive+no_connect"))
    )
    (net (code "80") (name "unconnected-(U11-PMEB-Pad33)") (class "Default")
      (node (ref "U11") (pin "33") (pinfunction "PMEB_33") (pintype "passive+no_connect"))
    )
    (net (code "81") (name "unconnected-(Y6-EC-Pad1)") (class "Default")
      (node (ref "Y6") (pin "1") (pinfunction "EC_1") (pintype "passive+no_connect"))
    )
    (net (code "82") (name "unconnected-(Y7-EC-Pad1)") (class "Default")
      (node (ref "Y7") (pin "1") (pinfunction "EC_1") (pintype "passive+no_connect"))
    )
  )
)
